# Board.net
KiCad netlist of a schematic drawn in EAGLE
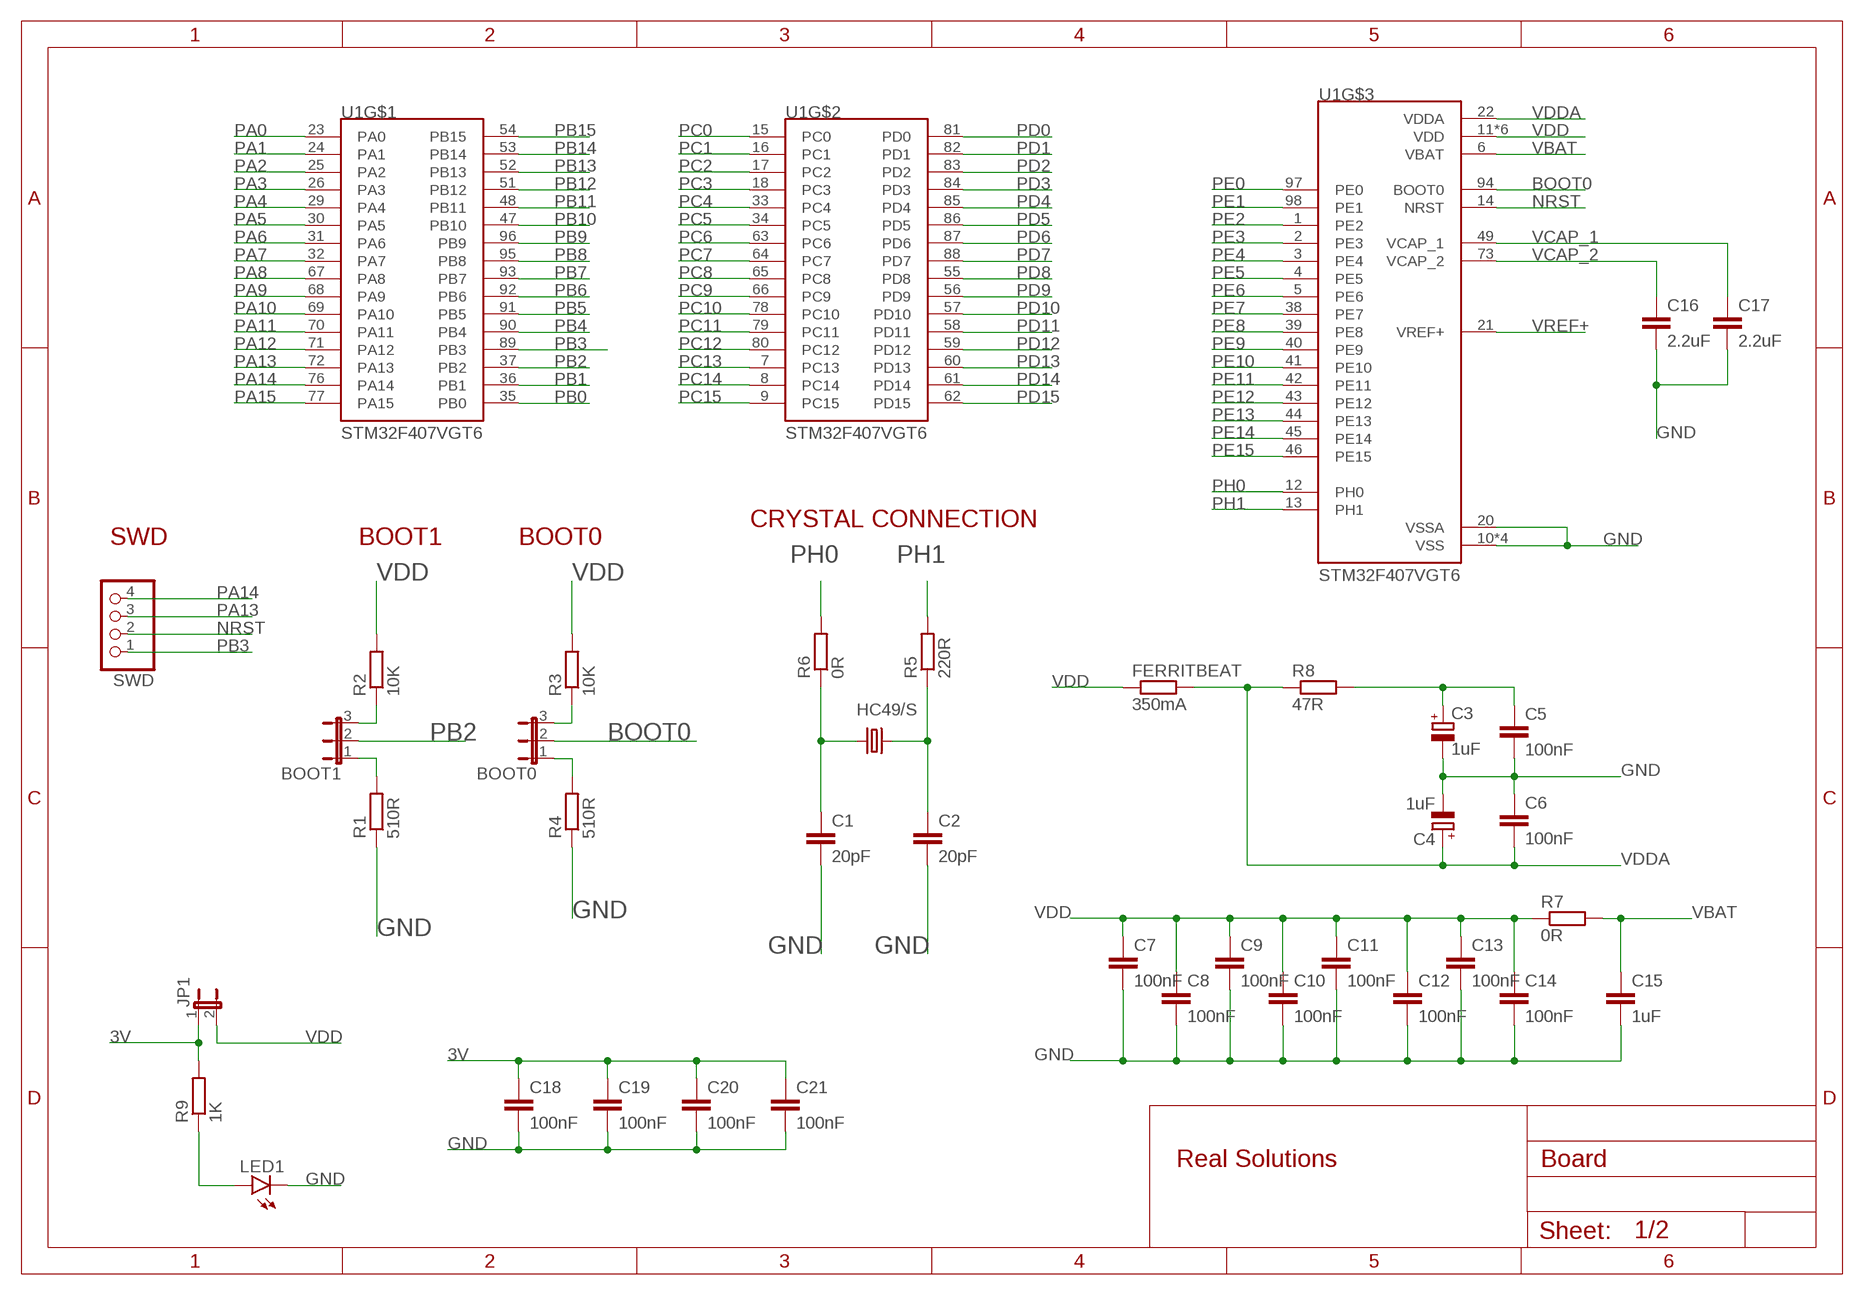
[diagram p0: schematic, sheet 1]
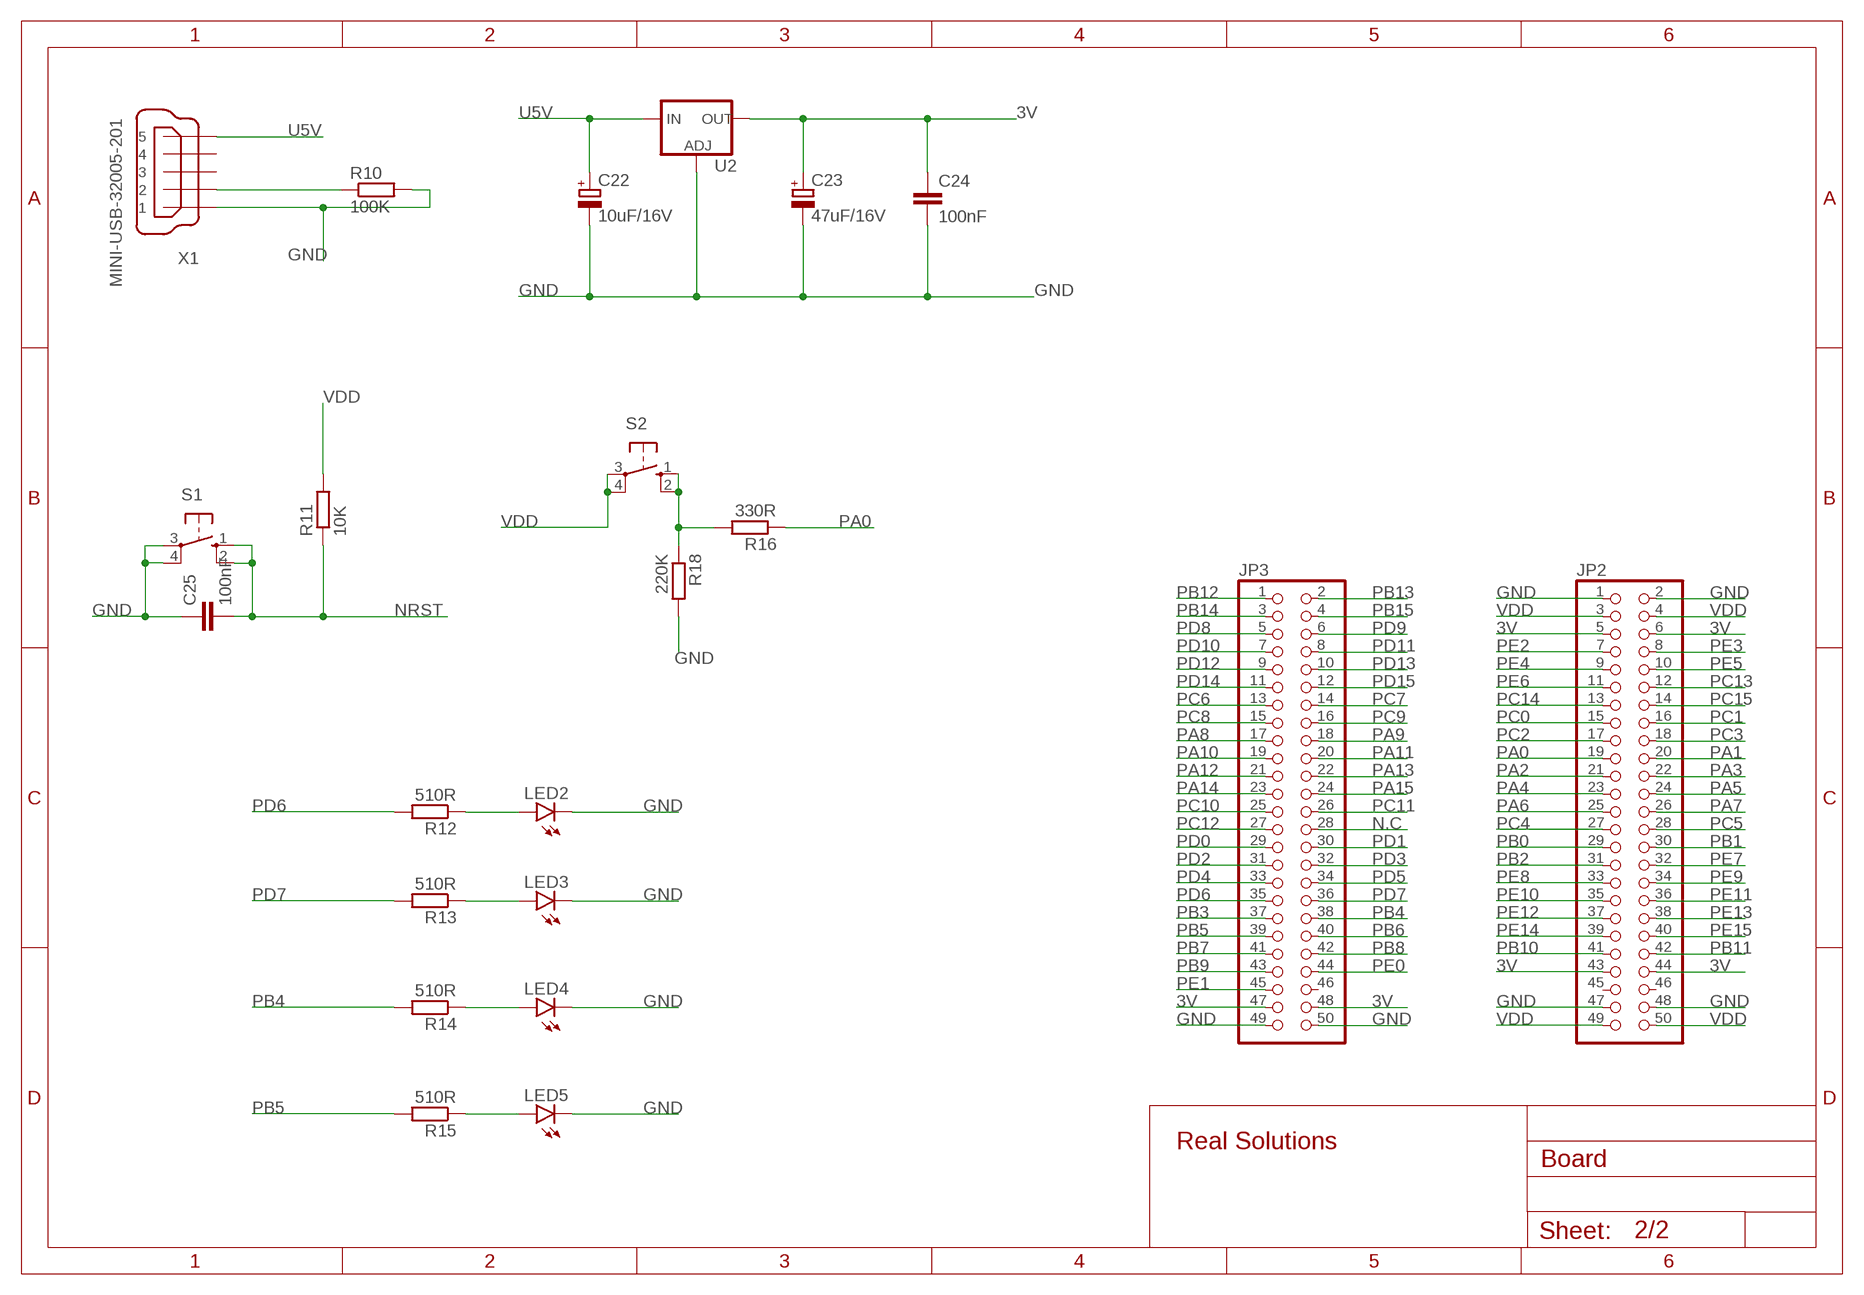
[diagram p1: schematic, sheet 2]

(export (version "E")
  (design (tool "Eeschema 10.0.6"))
  (components
    (comp (ref "BOOT0")
      (value "JP2E")
      (footprint "eagle-import:JP2")
      (libsource (lib "eagle-import") (part "JP2E"))
    )
    (comp (ref "BOOT1")
      (value "JP2E")
      (footprint "eagle-import:JP2")
      (libsource (lib "eagle-import") (part "JP2E"))
    )
    (comp (ref "C1")
      (value "20pF")
      (footprint "eagle-import:C0805")
      (libsource (lib "eagle-import") (part "C-EUC0805"))
    )
    (comp (ref "C2")
      (value "20pF")
      (footprint "eagle-import:C0805")
      (libsource (lib "eagle-import") (part "C-EUC0805"))
    )
    (comp (ref "C3")
      (value "1uF")
      (footprint "eagle-import:SMC_A")
      (libsource (lib "eagle-import") (part "CPOL-EUSMCA"))
    )
    (comp (ref "C4")
      (value "1uF")
      (footprint "eagle-import:SMC_A")
      (libsource (lib "eagle-import") (part "CPOL-EUSMCA"))
    )
    (comp (ref "C5")
      (value "100nF")
      (footprint "eagle-import:C0805")
      (libsource (lib "eagle-import") (part "C-EUC0805"))
    )
    (comp (ref "C6")
      (value "100nF")
      (footprint "eagle-import:C0805")
      (libsource (lib "eagle-import") (part "C-EUC0805"))
    )
    (comp (ref "C7")
      (value "100nF")
      (footprint "eagle-import:C0805")
      (libsource (lib "eagle-import") (part "C-EUC0805"))
    )
    (comp (ref "C8")
      (value "100nF")
      (footprint "eagle-import:C0805")
      (libsource (lib "eagle-import") (part "C-EUC0805"))
    )
    (comp (ref "C9")
      (value "100nF")
      (footprint "eagle-import:C0805")
      (libsource (lib "eagle-import") (part "C-EUC0805"))
    )
    (comp (ref "C10")
      (value "100nF")
      (footprint "eagle-import:C0805")
      (libsource (lib "eagle-import") (part "C-EUC0805"))
    )
    (comp (ref "C11")
      (value "100nF")
      (footprint "eagle-import:C0805")
      (libsource (lib "eagle-import") (part "C-EUC0805"))
    )
    (comp (ref "C12")
      (value "100nF")
      (footprint "eagle-import:C0805")
      (libsource (lib "eagle-import") (part "C-EUC0805"))
    )
    (comp (ref "C13")
      (value "100nF")
      (footprint "eagle-import:C0805")
      (libsource (lib "eagle-import") (part "C-EUC0805"))
    )
    (comp (ref "C14")
      (value "100nF")
      (footprint "eagle-import:C0805")
      (libsource (lib "eagle-import") (part "C-EUC0805"))
    )
    (comp (ref "C15")
      (value "1uF")
      (footprint "eagle-import:C0805")
      (libsource (lib "eagle-import") (part "C-EUC0805"))
    )
    (comp (ref "C16")
      (value "2.2uF")
      (footprint "eagle-import:C0805")
      (libsource (lib "eagle-import") (part "C-EUC0805"))
    )
    (comp (ref "C17")
      (value "2.2uF")
      (footprint "eagle-import:C0805")
      (libsource (lib "eagle-import") (part "C-EUC0805"))
    )
    (comp (ref "C18")
      (value "100nF")
      (footprint "eagle-import:C0805")
      (libsource (lib "eagle-import") (part "C-EUC0805"))
    )
    (comp (ref "C19")
      (value "100nF")
      (footprint "eagle-import:C0805")
      (libsource (lib "eagle-import") (part "C-EUC0805"))
    )
    (comp (ref "C20")
      (value "100nF")
      (footprint "eagle-import:C0805")
      (libsource (lib "eagle-import") (part "C-EUC0805"))
    )
    (comp (ref "C21")
      (value "100nF")
      (footprint "eagle-import:C0805")
      (libsource (lib "eagle-import") (part "C-EUC0805"))
    )
    (comp (ref "FERRITBEAT")
      (value "350mA")
      (footprint "eagle-import:R1206")
      (libsource (lib "eagle-import") (part "R-EU_R1206"))
    )
    (comp (ref "HC49/S")
      (value "CRYSTALHC49S")
      (footprint "eagle-import:HC49_S")
      (libsource (lib "eagle-import") (part "CRYSTALHC49S"))
    )
    (comp (ref "JP1")
      (value "JP1E")
      (footprint "eagle-import:JP1")
      (libsource (lib "eagle-import") (part "JP1E"))
    )
    (comp (ref "LED1")
      (value "LEDCHIP-LED0805")
      (footprint "eagle-import:CHIP-LED0805")
      (libsource (lib "eagle-import") (part "LEDCHIP-LED0805"))
    )
    (comp (ref "R1")
      (value "510R")
      (footprint "eagle-import:R0805")
      (libsource (lib "eagle-import") (part "R-EU_R0805"))
    )
    (comp (ref "R2")
      (value "10K")
      (footprint "eagle-import:R0805")
      (libsource (lib "eagle-import") (part "R-EU_R0805"))
    )
    (comp (ref "R3")
      (value "10K")
      (footprint "eagle-import:R0805")
      (libsource (lib "eagle-import") (part "R-EU_R0805"))
    )
    (comp (ref "R4")
      (value "510R")
      (footprint "eagle-import:R0805")
      (libsource (lib "eagle-import") (part "R-EU_R0805"))
    )
    (comp (ref "R5")
      (value "220R")
      (footprint "eagle-import:R0805")
      (libsource (lib "eagle-import") (part "R-EU_R0805"))
    )
    (comp (ref "R6")
      (value "0R")
      (footprint "eagle-import:R0805")
      (libsource (lib "eagle-import") (part "R-EU_R0805"))
    )
    (comp (ref "R7")
      (value "0R")
      (footprint "eagle-import:R0805")
      (libsource (lib "eagle-import") (part "R-EU_R0805"))
    )
    (comp (ref "R8")
      (value "47R")
      (footprint "eagle-import:R0805")
      (libsource (lib "eagle-import") (part "R-EU_R0805"))
    )
    (comp (ref "R9")
      (value "1K")
      (footprint "eagle-import:R0805")
      (libsource (lib "eagle-import") (part "R-EU_R0805"))
    )
    (comp (ref "SWD")
      (value "PINHD-1X4")
      (footprint "eagle-import:1X04")
      (libsource (lib "eagle-import") (part "PINHD-1X4"))
    )
    (comp (ref "U1")
      (value "STM32F407VGT6")
      (footprint "eagle-import:QFP50P1600X1600X160-100N")
      (fields (field (name "MF") "STMicroelectronics"))
      (libsource (lib "eagle-import") (part "STM32F407VGT6"))
    )
    (comp (ref "C22")
      (value "10uF/16V")
      (footprint "eagle-import:153CLV-0405")
      (libsource (lib "eagle-import") (part "CPOL-EU153CLV-0405"))
    )
    (comp (ref "C23")
      (value "47uF/16V")
      (footprint "eagle-import:153CLV-0605")
      (libsource (lib "eagle-import") (part "CPOL-EU153CLV-0605"))
    )
    (comp (ref "C24")
      (value "100nF")
      (footprint "eagle-import:C0805")
      (libsource (lib "eagle-import") (part "C-EUC0805"))
    )
    (comp (ref "C25")
      (value "100nF")
      (footprint "eagle-import:C0805")
      (libsource (lib "eagle-import") (part "C-EUC0805"))
    )
    (comp (ref "JP2")
      (value "PINHD-2X25")
      (footprint "eagle-import:2X25")
      (libsource (lib "eagle-import") (part "PINHD-2X25"))
    )
    (comp (ref "JP3")
      (value "PINHD-2X25")
      (footprint "eagle-import:2X25")
      (libsource (lib "eagle-import") (part "PINHD-2X25"))
    )
    (comp (ref "LED2")
      (value "LEDCHIP-LED0805")
      (footprint "eagle-import:CHIP-LED0805")
      (libsource (lib "eagle-import") (part "LEDCHIP-LED0805"))
    )
    (comp (ref "LED3")
      (value "LEDCHIP-LED0805")
      (footprint "eagle-import:CHIP-LED0805")
      (libsource (lib "eagle-import") (part "LEDCHIP-LED0805"))
    )
    (comp (ref "LED4")
      (value "LEDCHIP-LED0805")
      (footprint "eagle-import:CHIP-LED0805")
      (libsource (lib "eagle-import") (part "LEDCHIP-LED0805"))
    )
    (comp (ref "LED5")
      (value "LEDCHIP-LED0805")
      (footprint "eagle-import:CHIP-LED0805")
      (libsource (lib "eagle-import") (part "LEDCHIP-LED0805"))
    )
    (comp (ref "R10")
      (value "100K")
      (footprint "eagle-import:R0805")
      (libsource (lib "eagle-import") (part "R-EU_R0805"))
    )
    (comp (ref "R11")
      (value "10K")
      (footprint "eagle-import:R0805")
      (libsource (lib "eagle-import") (part "R-EU_R0805"))
    )
    (comp (ref "R12")
      (value "510R")
      (footprint "eagle-import:R0805")
      (libsource (lib "eagle-import") (part "R-EU_R0805"))
    )
    (comp (ref "R13")
      (value "510R")
      (footprint "eagle-import:R0805")
      (libsource (lib "eagle-import") (part "R-EU_R0805"))
    )
    (comp (ref "R14")
      (value "510R")
      (footprint "eagle-import:R0805")
      (libsource (lib "eagle-import") (part "R-EU_R0805"))
    )
    (comp (ref "R15")
      (value "510R")
      (footprint "eagle-import:R0805")
      (libsource (lib "eagle-import") (part "R-EU_R0805"))
    )
    (comp (ref "R16")
      (value "330R")
      (footprint "eagle-import:R0805")
      (libsource (lib "eagle-import") (part "R-EU_R0805"))
    )
    (comp (ref "R18")
      (value "220K")
      (footprint "eagle-import:R0805")
      (libsource (lib "eagle-import") (part "R-EU_R0805"))
    )
    (comp (ref "S1")
      (value "10-XX")
      (footprint "eagle-import:B3F-10XX")
      (fields (field (name "MPN") "B3F-1000"))
      (libsource (lib "eagle-import") (part "10-XX"))
    )
    (comp (ref "S2")
      (value "10-XX")
      (footprint "eagle-import:B3F-10XX")
      (fields (field (name "MPN") "B3F-1000"))
      (libsource (lib "eagle-import") (part "10-XX"))
    )
    (comp (ref "U2")
      (value "V_REG_LM1117SOT223")
      (footprint "eagle-import:SOT223")
      (libsource (lib "eagle-import") (part "V_REG_LM1117SOT223"))
    )
    (comp (ref "X1")
      (value "MINI-USB-32005-201")
      (footprint "eagle-import:32005-201")
      (libsource (lib "eagle-import") (part "MINI-USB-32005-201"))
    )
  )
  (nets
    (net (code "1") (name "3V") (class "Default")
      (node (ref "C18") (pin "1") (pinfunction "1_1") (pintype "passive"))
      (node (ref "C19") (pin "1") (pinfunction "1_1") (pintype "passive"))
      (node (ref "C20") (pin "1") (pinfunction "1_1") (pintype "passive"))
      (node (ref "C21") (pin "1") (pinfunction "1_1") (pintype "passive"))
      (node (ref "C23") (pin "+") (pinfunction "+_+") (pintype "passive"))
      (node (ref "C24") (pin "1") (pinfunction "1_1") (pintype "passive"))
      (node (ref "JP1") (pin "1") (pinfunction "1_1") (pintype "passive"))
      (node (ref "JP2") (pin "43") (pinfunction "43_43") (pintype "passive"))
      (node (ref "JP2") (pin "44") (pinfunction "44_44") (pintype "passive"))
      (node (ref "JP2") (pin "5") (pinfunction "5_5") (pintype "passive"))
      (node (ref "JP2") (pin "6") (pinfunction "6_6") (pintype "passive"))
      (node (ref "JP3") (pin "47") (pinfunction "47_47") (pintype "passive"))
      (node (ref "JP3") (pin "48") (pinfunction "48_48") (pintype "passive"))
      (node (ref "R9") (pin "2") (pinfunction "2_2") (pintype "passive"))
      (node (ref "U2") (pin "2") (pinfunction "OUT_2") (pintype "output"))
      (node (ref "U2") (pin "4") (pinfunction "OUT_4") (pintype "output"))
    )
    (net (code "2") (name "BOOT0") (class "Default")
      (node (ref "BOOT0") (pin "2") (pinfunction "2_2") (pintype "passive"))
      (node (ref "U1") (pin "94") (pinfunction "BOOT0_94") (pintype "input"))
    )
    (net (code "3") (name "GND") (class "Default")
      (node (ref "C1") (pin "2") (pinfunction "2_2") (pintype "passive"))
      (node (ref "C10") (pin "2") (pinfunction "2_2") (pintype "passive"))
      (node (ref "C11") (pin "2") (pinfunction "2_2") (pintype "passive"))
      (node (ref "C12") (pin "2") (pinfunction "2_2") (pintype "passive"))
      (node (ref "C13") (pin "2") (pinfunction "2_2") (pintype "passive"))
      (node (ref "C14") (pin "2") (pinfunction "2_2") (pintype "passive"))
      (node (ref "C15") (pin "2") (pinfunction "2_2") (pintype "passive"))
      (node (ref "C16") (pin "2") (pinfunction "2_2") (pintype "passive"))
      (node (ref "C17") (pin "2") (pinfunction "2_2") (pintype "passive"))
      (node (ref "C18") (pin "2") (pinfunction "2_2") (pintype "passive"))
      (node (ref "C19") (pin "2") (pinfunction "2_2") (pintype "passive"))
      (node (ref "C2") (pin "2") (pinfunction "2_2") (pintype "passive"))
      (node (ref "C20") (pin "2") (pinfunction "2_2") (pintype "passive"))
      (node (ref "C21") (pin "2") (pinfunction "2_2") (pintype "passive"))
      (node (ref "C22") (pin "-") (pinfunction "-_-") (pintype "passive"))
      (node (ref "C23") (pin "-") (pinfunction "-_-") (pintype "passive"))
      (node (ref "C24") (pin "2") (pinfunction "2_2") (pintype "passive"))
      (node (ref "C25") (pin "1") (pinfunction "1_1") (pintype "passive"))
      (node (ref "C3") (pin "-") (pinfunction "-_-") (pintype "passive"))
      (node (ref "C4") (pin "-") (pinfunction "-_-") (pintype "passive"))
      (node (ref "C5") (pin "2") (pinfunction "2_2") (pintype "passive"))
      (node (ref "C6") (pin "1") (pinfunction "1_1") (pintype "passive"))
      (node (ref "C7") (pin "2") (pinfunction "2_2") (pintype "passive"))
      (node (ref "C8") (pin "2") (pinfunction "2_2") (pintype "passive"))
      (node (ref "C9") (pin "2") (pinfunction "2_2") (pintype "passive"))
      (node (ref "JP2") (pin "1") (pinfunction "1_1") (pintype "passive"))
      (node (ref "JP2") (pin "2") (pinfunction "2_2") (pintype "passive"))
      (node (ref "JP2") (pin "47") (pinfunction "47_47") (pintype "passive"))
      (node (ref "JP2") (pin "48") (pinfunction "48_48") (pintype "passive"))
      (node (ref "JP3") (pin "49") (pinfunction "49_49") (pintype "passive"))
      (node (ref "JP3") (pin "50") (pinfunction "50_50") (pintype "passive"))
      (node (ref "LED1") (pin "C") (pinfunction "C_C") (pintype "passive"))
      (node (ref "LED2") (pin "C") (pinfunction "C_C") (pintype "passive"))
      (node (ref "LED3") (pin "C") (pinfunction "C_C") (pintype "passive"))
      (node (ref "LED4") (pin "C") (pinfunction "C_C") (pintype "passive"))
      (node (ref "LED5") (pin "C") (pinfunction "C_C") (pintype "passive"))
      (node (ref "R1") (pin "1") (pinfunction "1_1") (pintype "passive"))
      (node (ref "R10") (pin "2") (pinfunction "2_2") (pintype "passive"))
      (node (ref "R18") (pin "2") (pinfunction "2_2") (pintype "passive"))
      (node (ref "R4") (pin "1") (pinfunction "1_1") (pintype "passive"))
      (node (ref "S1") (pin "3") (pinfunction "P_3") (pintype "passive"))
      (node (ref "S1") (pin "4") (pinfunction "P1_4") (pintype "passive"))
      (node (ref "U1") (pin "10") (pinfunction "VSS_10") (pintype "power_in"))
      (node (ref "U1") (pin "20") (pinfunction "VSSA_20") (pintype "power_in"))
      (node (ref "U1") (pin "27") (pinfunction "VSS_27") (pintype "power_in"))
      (node (ref "U1") (pin "74") (pinfunction "VSS_74") (pintype "power_in"))
      (node (ref "U1") (pin "99") (pinfunction "VSS_99") (pintype "power_in"))
      (node (ref "U2") (pin "1") (pinfunction "ADJ_1") (pintype "input"))
      (node (ref "X1") (pin "1") (pinfunction "1_1") (pintype "passive"))
    )
    (net (code "4") (name "N.C") (class "Default")
      (node (ref "JP3") (pin "28") (pinfunction "28_28") (pintype "passive"))
    )
    (net (code "5") (name "NRST") (class "Default")
      (node (ref "C25") (pin "2") (pinfunction "2_2") (pintype "passive"))
      (node (ref "R11") (pin "1") (pinfunction "1_1") (pintype "passive"))
      (node (ref "S1") (pin "1") (pinfunction "S_1") (pintype "passive"))
      (node (ref "S1") (pin "2") (pinfunction "S1_2") (pintype "passive"))
      (node (ref "SWD") (pin "2") (pinfunction "2_2") (pintype "passive"))
      (node (ref "U1") (pin "14") (pinfunction "NRST_14") (pintype "bidirectional"))
    )
    (net (code "6") (name "Net-(BOOT0-Pad1)") (class "Default")
      (node (ref "BOOT0") (pin "1") (pinfunction "1_1") (pintype "passive"))
      (node (ref "R4") (pin "2") (pinfunction "2_2") (pintype "passive"))
    )
    (net (code "7") (name "Net-(BOOT0-Pad3)") (class "Default")
      (node (ref "BOOT0") (pin "3") (pinfunction "3_3") (pintype "passive"))
      (node (ref "R3") (pin "1") (pinfunction "1_1") (pintype "passive"))
    )
    (net (code "8") (name "Net-(BOOT1-Pad1)") (class "Default")
      (node (ref "BOOT1") (pin "1") (pinfunction "1_1") (pintype "passive"))
      (node (ref "R1") (pin "2") (pinfunction "2_2") (pintype "passive"))
    )
    (net (code "9") (name "Net-(BOOT1-Pad3)") (class "Default")
      (node (ref "BOOT1") (pin "3") (pinfunction "3_3") (pintype "passive"))
      (node (ref "R2") (pin "1") (pinfunction "1_1") (pintype "passive"))
    )
    (net (code "10") (name "Net-(C1-Pad1)") (class "Default")
      (node (ref "C1") (pin "1") (pinfunction "1_1") (pintype "passive"))
      (node (ref "HC49/S") (pin "1") (pinfunction "1_1") (pintype "passive"))
      (node (ref "R6") (pin "1") (pinfunction "1_1") (pintype "passive"))
    )
    (net (code "11") (name "Net-(C2-Pad1)") (class "Default")
      (node (ref "C2") (pin "1") (pinfunction "1_1") (pintype "passive"))
      (node (ref "HC49/S") (pin "2") (pinfunction "2_2") (pintype "passive"))
      (node (ref "R5") (pin "1") (pinfunction "1_1") (pintype "passive"))
    )
    (net (code "12") (name "Net-(C3-Pad+)") (class "Default")
      (node (ref "C3") (pin "+") (pinfunction "+_+") (pintype "passive"))
      (node (ref "C5") (pin "1") (pinfunction "1_1") (pintype "passive"))
      (node (ref "R8") (pin "2") (pinfunction "2_2") (pintype "passive"))
    )
    (net (code "13") (name "Net-(LED1-PadA)") (class "Default")
      (node (ref "LED1") (pin "A") (pinfunction "A_A") (pintype "passive"))
      (node (ref "R9") (pin "1") (pinfunction "1_1") (pintype "passive"))
    )
    (net (code "14") (name "Net-(LED2-PadA)") (class "Default")
      (node (ref "LED2") (pin "A") (pinfunction "A_A") (pintype "passive"))
      (node (ref "R12") (pin "1") (pinfunction "1_1") (pintype "passive"))
    )
    (net (code "15") (name "Net-(LED3-PadA)") (class "Default")
      (node (ref "LED3") (pin "A") (pinfunction "A_A") (pintype "passive"))
      (node (ref "R13") (pin "1") (pinfunction "1_1") (pintype "passive"))
    )
    (net (code "16") (name "Net-(LED4-PadA)") (class "Default")
      (node (ref "LED4") (pin "A") (pinfunction "A_A") (pintype "passive"))
      (node (ref "R14") (pin "1") (pinfunction "1_1") (pintype "passive"))
    )
    (net (code "17") (name "Net-(LED5-PadA)") (class "Default")
      (node (ref "LED5") (pin "A") (pinfunction "A_A") (pintype "passive"))
      (node (ref "R15") (pin "1") (pinfunction "1_1") (pintype "passive"))
    )
    (net (code "18") (name "Net-(R10-Pad1)") (class "Default")
      (node (ref "R10") (pin "1") (pinfunction "1_1") (pintype "passive"))
      (node (ref "X1") (pin "2") (pinfunction "2_2") (pintype "passive"))
    )
    (net (code "19") (name "Net-(S2-S)") (class "Default")
      (node (ref "R16") (pin "2") (pinfunction "2_2") (pintype "passive"))
      (node (ref "R18") (pin "1") (pinfunction "1_1") (pintype "passive"))
      (node (ref "S2") (pin "1") (pinfunction "S_1") (pintype "passive"))
      (node (ref "S2") (pin "2") (pinfunction "S1_2") (pintype "passive"))
    )
    (net (code "20") (name "PA0") (class "Default")
      (node (ref "JP2") (pin "19") (pinfunction "19_19") (pintype "passive"))
      (node (ref "R16") (pin "1") (pinfunction "1_1") (pintype "passive"))
      (node (ref "U1") (pin "23") (pinfunction "PA0_23") (pintype "bidirectional"))
    )
    (net (code "21") (name "PA1") (class "Default")
      (node (ref "JP2") (pin "20") (pinfunction "20_20") (pintype "passive"))
      (node (ref "U1") (pin "24") (pinfunction "PA1_24") (pintype "bidirectional"))
    )
    (net (code "22") (name "PA2") (class "Default")
      (node (ref "JP2") (pin "21") (pinfunction "21_21") (pintype "passive"))
      (node (ref "U1") (pin "25") (pinfunction "PA2_25") (pintype "bidirectional"))
    )
    (net (code "23") (name "PA3") (class "Default")
      (node (ref "JP2") (pin "22") (pinfunction "22_22") (pintype "passive"))
      (node (ref "U1") (pin "26") (pinfunction "PA3_26") (pintype "bidirectional"))
    )
    (net (code "24") (name "PA4") (class "Default")
      (node (ref "JP2") (pin "23") (pinfunction "23_23") (pintype "passive"))
      (node (ref "U1") (pin "29") (pinfunction "PA4_29") (pintype "bidirectional"))
    )
    (net (code "25") (name "PA5") (class "Default")
      (node (ref "JP2") (pin "24") (pinfunction "24_24") (pintype "passive"))
      (node (ref "U1") (pin "30") (pinfunction "PA5_30") (pintype "bidirectional"))
    )
    (net (code "26") (name "PA6") (class "Default")
      (node (ref "JP2") (pin "25") (pinfunction "25_25") (pintype "passive"))
      (node (ref "U1") (pin "31") (pinfunction "PA6_31") (pintype "bidirectional"))
    )
    (net (code "27") (name "PA7") (class "Default")
      (node (ref "JP2") (pin "26") (pinfunction "26_26") (pintype "passive"))
      (node (ref "U1") (pin "32") (pinfunction "PA7_32") (pintype "bidirectional"))
    )
    (net (code "28") (name "PA8") (class "Default")
      (node (ref "JP3") (pin "17") (pinfunction "17_17") (pintype "passive"))
      (node (ref "U1") (pin "67") (pinfunction "PA8_67") (pintype "bidirectional"))
    )
    (net (code "29") (name "PA9") (class "Default")
      (node (ref "JP3") (pin "18") (pinfunction "18_18") (pintype "passive"))
      (node (ref "U1") (pin "68") (pinfunction "PA9_68") (pintype "bidirectional"))
    )
    (net (code "30") (name "PA10") (class "Default")
      (node (ref "JP3") (pin "19") (pinfunction "19_19") (pintype "passive"))
      (node (ref "U1") (pin "69") (pinfunction "PA10_69") (pintype "bidirectional"))
    )
    (net (code "31") (name "PA11") (class "Default")
      (node (ref "JP3") (pin "20") (pinfunction "20_20") (pintype "passive"))
      (node (ref "U1") (pin "70") (pinfunction "PA11_70") (pintype "bidirectional"))
    )
    (net (code "32") (name "PA12") (class "Default")
      (node (ref "JP3") (pin "21") (pinfunction "21_21") (pintype "passive"))
      (node (ref "U1") (pin "71") (pinfunction "PA12_71") (pintype "bidirectional"))
    )
    (net (code "33") (name "PA13") (class "Default")
      (node (ref "JP3") (pin "22") (pinfunction "22_22") (pintype "passive"))
      (node (ref "SWD") (pin "3") (pinfunction "3_3") (pintype "passive"))
      (node (ref "U1") (pin "72") (pinfunction "PA13_72") (pintype "bidirectional"))
    )
    (net (code "34") (name "PA14") (class "Default")
      (node (ref "JP3") (pin "23") (pinfunction "23_23") (pintype "passive"))
      (node (ref "SWD") (pin "4") (pinfunction "4_4") (pintype "passive"))
      (node (ref "U1") (pin "76") (pinfunction "PA14_76") (pintype "bidirectional"))
    )
    (net (code "35") (name "PA15") (class "Default")
      (node (ref "JP3") (pin "24") (pinfunction "24_24") (pintype "passive"))
      (node (ref "U1") (pin "77") (pinfunction "PA15_77") (pintype "bidirectional"))
    )
    (net (code "36") (name "PB0") (class "Default")
      (node (ref "JP2") (pin "29") (pinfunction "29_29") (pintype "passive"))
      (node (ref "U1") (pin "35") (pinfunction "PB0_35") (pintype "bidirectional"))
    )
    (net (code "37") (name "PB1") (class "Default")
      (node (ref "JP2") (pin "30") (pinfunction "30_30") (pintype "passive"))
      (node (ref "U1") (pin "36") (pinfunction "PB1_36") (pintype "bidirectional"))
    )
    (net (code "38") (name "PB2") (class "Default")
      (node (ref "BOOT1") (pin "2") (pinfunction "2_2") (pintype "passive"))
      (node (ref "JP2") (pin "31") (pinfunction "31_31") (pintype "passive"))
      (node (ref "U1") (pin "37") (pinfunction "PB2_37") (pintype "bidirectional"))
    )
    (net (code "39") (name "PB3") (class "Default")
      (node (ref "JP3") (pin "37") (pinfunction "37_37") (pintype "passive"))
      (node (ref "SWD") (pin "1") (pinfunction "1_1") (pintype "passive"))
      (node (ref "U1") (pin "89") (pinfunction "PB3_89") (pintype "bidirectional"))
    )
    (net (code "40") (name "PB4") (class "Default")
      (node (ref "JP3") (pin "38") (pinfunction "38_38") (pintype "passive"))
      (node (ref "R14") (pin "2") (pinfunction "2_2") (pintype "passive"))
      (node (ref "U1") (pin "90") (pinfunction "PB4_90") (pintype "bidirectional"))
    )
    (net (code "41") (name "PB5") (class "Default")
      (node (ref "JP3") (pin "39") (pinfunction "39_39") (pintype "passive"))
      (node (ref "R15") (pin "2") (pinfunction "2_2") (pintype "passive"))
      (node (ref "U1") (pin "91") (pinfunction "PB5_91") (pintype "bidirectional"))
    )
    (net (code "42") (name "PB6") (class "Default")
      (node (ref "JP3") (pin "40") (pinfunction "40_40") (pintype "passive"))
      (node (ref "U1") (pin "92") (pinfunction "PB6_92") (pintype "bidirectional"))
    )
    (net (code "43") (name "PB7") (class "Default")
      (node (ref "JP3") (pin "41") (pinfunction "41_41") (pintype "passive"))
      (node (ref "U1") (pin "93") (pinfunction "PB7_93") (pintype "bidirectional"))
    )
    (net (code "44") (name "PB8") (class "Default")
      (node (ref "JP3") (pin "42") (pinfunction "42_42") (pintype "passive"))
      (node (ref "U1") (pin "95") (pinfunction "PB8_95") (pintype "bidirectional"))
    )
    (net (code "45") (name "PB9") (class "Default")
      (node (ref "JP3") (pin "43") (pinfunction "43_43") (pintype "passive"))
      (node (ref "U1") (pin "96") (pinfunction "PB9_96") (pintype "bidirectional"))
    )
    (net (code "46") (name "PB10") (class "Default")
      (node (ref "JP2") (pin "41") (pinfunction "41_41") (pintype "passive"))
      (node (ref "U1") (pin "47") (pinfunction "PB10_47") (pintype "bidirectional"))
    )
    (net (code "47") (name "PB11") (class "Default")
      (node (ref "JP2") (pin "42") (pinfunction "42_42") (pintype "passive"))
      (node (ref "U1") (pin "48") (pinfunction "PB11_48") (pintype "bidirectional"))
    )
    (net (code "48") (name "PB12") (class "Default")
      (node (ref "JP3") (pin "1") (pinfunction "1_1") (pintype "passive"))
      (node (ref "U1") (pin "51") (pinfunction "PB12_51") (pintype "bidirectional"))
    )
    (net (code "49") (name "PB13") (class "Default")
      (node (ref "JP3") (pin "2") (pinfunction "2_2") (pintype "passive"))
      (node (ref "U1") (pin "52") (pinfunction "PB13_52") (pintype "bidirectional"))
    )
    (net (code "50") (name "PB14") (class "Default")
      (node (ref "JP3") (pin "3") (pinfunction "3_3") (pintype "passive"))
      (node (ref "U1") (pin "53") (pinfunction "PB14_53") (pintype "bidirectional"))
    )
    (net (code "51") (name "PB15") (class "Default")
      (node (ref "JP3") (pin "4") (pinfunction "4_4") (pintype "passive"))
      (node (ref "U1") (pin "54") (pinfunction "PB15_54") (pintype "bidirectional"))
    )
    (net (code "52") (name "PC0") (class "Default")
      (node (ref "JP2") (pin "15") (pinfunction "15_15") (pintype "passive"))
      (node (ref "U1") (pin "15") (pinfunction "PC0_15") (pintype "bidirectional"))
    )
    (net (code "53") (name "PC1") (class "Default")
      (node (ref "JP2") (pin "16") (pinfunction "16_16") (pintype "passive"))
      (node (ref "U1") (pin "16") (pinfunction "PC1_16") (pintype "bidirectional"))
    )
    (net (code "54") (name "PC2") (class "Default")
      (node (ref "JP2") (pin "17") (pinfunction "17_17") (pintype "passive"))
      (node (ref "U1") (pin "17") (pinfunction "PC2_17") (pintype "bidirectional"))
    )
    (net (code "55") (name "PC3") (class "Default")
      (node (ref "JP2") (pin "18") (pinfunction "18_18") (pintype "passive"))
      (node (ref "U1") (pin "18") (pinfunction "PC3_18") (pintype "bidirectional"))
    )
    (net (code "56") (name "PC4") (class "Default")
      (node (ref "JP2") (pin "27") (pinfunction "27_27") (pintype "passive"))
      (node (ref "U1") (pin "33") (pinfunction "PC4_33") (pintype "bidirectional"))
    )
    (net (code "57") (name "PC5") (class "Default")
      (node (ref "JP2") (pin "28") (pinfunction "28_28") (pintype "passive"))
      (node (ref "U1") (pin "34") (pinfunction "PC5_34") (pintype "bidirectional"))
    )
    (net (code "58") (name "PC6") (class "Default")
      (node (ref "JP3") (pin "13") (pinfunction "13_13") (pintype "passive"))
      (node (ref "U1") (pin "63") (pinfunction "PC6_63") (pintype "bidirectional"))
    )
    (net (code "59") (name "PC7") (class "Default")
      (node (ref "JP3") (pin "14") (pinfunction "14_14") (pintype "passive"))
      (node (ref "U1") (pin "64") (pinfunction "PC7_64") (pintype "bidirectional"))
    )
    (net (code "60") (name "PC8") (class "Default")
      (node (ref "JP3") (pin "15") (pinfunction "15_15") (pintype "passive"))
      (node (ref "U1") (pin "65") (pinfunction "PC8_65") (pintype "bidirectional"))
    )
    (net (code "61") (name "PC9") (class "Default")
      (node (ref "JP3") (pin "16") (pinfunction "16_16") (pintype "passive"))
      (node (ref "U1") (pin "66") (pinfunction "PC9_66") (pintype "bidirectional"))
    )
    (net (code "62") (name "PC10") (class "Default")
      (node (ref "JP3") (pin "25") (pinfunction "25_25") (pintype "passive"))
      (node (ref "U1") (pin "78") (pinfunction "PC10_78") (pintype "bidirectional"))
    )
    (net (code "63") (name "PC11") (class "Default")
      (node (ref "JP3") (pin "26") (pinfunction "26_26") (pintype "passive"))
      (node (ref "U1") (pin "79") (pinfunction "PC11_79") (pintype "bidirectional"))
    )
    (net (code "64") (name "PC12") (class "Default")
      (node (ref "JP3") (pin "27") (pinfunction "27_27") (pintype "passive"))
      (node (ref "U1") (pin "80") (pinfunction "PC12_80") (pintype "bidirectional"))
    )
    (net (code "65") (name "PC13") (class "Default")
      (node (ref "JP2") (pin "12") (pinfunction "12_12") (pintype "passive"))
      (node (ref "U1") (pin "7") (pinfunction "PC13_7") (pintype "bidirectional"))
    )
    (net (code "66") (name "PC14") (class "Default")
      (node (ref "JP2") (pin "13") (pinfunction "13_13") (pintype "passive"))
      (node (ref "U1") (pin "8") (pinfunction "PC14_8") (pintype "bidirectional"))
    )
    (net (code "67") (name "PC15") (class "Default")
      (node (ref "JP2") (pin "14") (pinfunction "14_14") (pintype "passive"))
      (node (ref "U1") (pin "9") (pinfunction "PC15_9") (pintype "bidirectional"))
    )
    (net (code "68") (name "PD0") (class "Default")
      (node (ref "JP3") (pin "29") (pinfunction "29_29") (pintype "passive"))
      (node (ref "U1") (pin "81") (pinfunction "PD0_81") (pintype "bidirectional"))
    )
    (net (code "69") (name "PD1") (class "Default")
      (node (ref "JP3") (pin "30") (pinfunction "30_30") (pintype "passive"))
      (node (ref "U1") (pin "82") (pinfunction "PD1_82") (pintype "bidirectional"))
    )
    (net (code "70") (name "PD2") (class "Default")
      (node (ref "JP3") (pin "31") (pinfunction "31_31") (pintype "passive"))
      (node (ref "U1") (pin "83") (pinfunction "PD2_83") (pintype "bidirectional"))
    )
    (net (code "71") (name "PD3") (class "Default")
      (node (ref "JP3") (pin "32") (pinfunction "32_32") (pintype "passive"))
      (node (ref "U1") (pin "84") (pinfunction "PD3_84") (pintype "bidirectional"))
    )
    (net (code "72") (name "PD4") (class "Default")
      (node (ref "JP3") (pin "33") (pinfunction "33_33") (pintype "passive"))
      (node (ref "U1") (pin "85") (pinfunction "PD4_85") (pintype "bidirectional"))
    )
    (net (code "73") (name "PD5") (class "Default")
      (node (ref "JP3") (pin "34") (pinfunction "34_34") (pintype "passive"))
      (node (ref "U1") (pin "86") (pinfunction "PD5_86") (pintype "bidirectional"))
    )
    (net (code "74") (name "PD6") (class "Default")
      (node (ref "JP3") (pin "35") (pinfunction "35_35") (pintype "passive"))
      (node (ref "R12") (pin "2") (pinfunction "2_2") (pintype "passive"))
      (node (ref "U1") (pin "87") (pinfunction "PD6_87") (pintype "bidirectional"))
    )
    (net (code "75") (name "PD7") (class "Default")
      (node (ref "JP3") (pin "36") (pinfunction "36_36") (pintype "passive"))
      (node (ref "R13") (pin "2") (pinfunction "2_2") (pintype "passive"))
      (node (ref "U1") (pin "88") (pinfunction "PD7_88") (pintype "bidirectional"))
    )
    (net (code "76") (name "PD8") (class "Default")
      (node (ref "JP3") (pin "5") (pinfunction "5_5") (pintype "passive"))
      (node (ref "U1") (pin "55") (pinfunction "PD8_55") (pintype "bidirectional"))
    )
    (net (code "77") (name "PD9") (class "Default")
      (node (ref "JP3") (pin "6") (pinfunction "6_6") (pintype "passive"))
      (node (ref "U1") (pin "56") (pinfunction "PD9_56") (pintype "bidirectional"))
    )
    (net (code "78") (name "PD10") (class "Default")
      (node (ref "JP3") (pin "7") (pinfunction "7_7") (pintype "passive"))
      (node (ref "U1") (pin "57") (pinfunction "PD10_57") (pintype "bidirectional"))
    )
    (net (code "79") (name "PD11") (class "Default")
      (node (ref "JP3") (pin "8") (pinfunction "8_8") (pintype "passive"))
      (node (ref "U1") (pin "58") (pinfunction "PD11_58") (pintype "bidirectional"))
    )
    (net (code "80") (name "PD12") (class "Default")
      (node (ref "JP3") (pin "9") (pinfunction "9_9") (pintype "passive"))
      (node (ref "U1") (pin "59") (pinfunction "PD12_59") (pintype "bidirectional"))
    )
    (net (code "81") (name "PD13") (class "Default")
      (node (ref "JP3") (pin "10") (pinfunction "10_10") (pintype "passive"))
      (node (ref "U1") (pin "60") (pinfunction "PD13_60") (pintype "bidirectional"))
    )
    (net (code "82") (name "PD14") (class "Default")
      (node (ref "JP3") (pin "11") (pinfunction "11_11") (pintype "passive"))
      (node (ref "U1") (pin "61") (pinfunction "PD14_61") (pintype "bidirectional"))
    )
    (net (code "83") (name "PD15") (class "Default")
      (node (ref "JP3") (pin "12") (pinfunction "12_12") (pintype "passive"))
      (node (ref "U1") (pin "62") (pinfunction "PD15_62") (pintype "bidirectional"))
    )
    (net (code "84") (name "PE0") (class "Default")
      (node (ref "JP3") (pin "44") (pinfunction "44_44") (pintype "passive"))
      (node (ref "U1") (pin "97") (pinfunction "PE0_97") (pintype "bidirectional"))
    )
    (net (code "85") (name "PE1") (class "Default")
      (node (ref "JP3") (pin "45") (pinfunction "45_45") (pintype "passive"))
      (node (ref "U1") (pin "98") (pinfunction "PE1_98") (pintype "bidirectional"))
    )
    (net (code "86") (name "PE2") (class "Default")
      (node (ref "JP2") (pin "7") (pinfunction "7_7") (pintype "passive"))
      (node (ref "U1") (pin "1") (pinfunction "PE2_1") (pintype "bidirectional"))
    )
    (net (code "87") (name "PE3") (class "Default")
      (node (ref "JP2") (pin "8") (pinfunction "8_8") (pintype "passive"))
      (node (ref "U1") (pin "2") (pinfunction "PE3_2") (pintype "bidirectional"))
    )
    (net (code "88") (name "PE4") (class "Default")
      (node (ref "JP2") (pin "9") (pinfunction "9_9") (pintype "passive"))
      (node (ref "U1") (pin "3") (pinfunction "PE4_3") (pintype "bidirectional"))
    )
    (net (code "89") (name "PE5") (class "Default")
      (node (ref "JP2") (pin "10") (pinfunction "10_10") (pintype "passive"))
      (node (ref "U1") (pin "4") (pinfunction "PE5_4") (pintype "bidirectional"))
    )
    (net (code "90") (name "PE6") (class "Default")
      (node (ref "JP2") (pin "11") (pinfunction "11_11") (pintype "passive"))
      (node (ref "U1") (pin "5") (pinfunction "PE6_5") (pintype "bidirectional"))
    )
    (net (code "91") (name "PE7") (class "Default")
      (node (ref "JP2") (pin "32") (pinfunction "32_32") (pintype "passive"))
      (node (ref "U1") (pin "38") (pinfunction "PE7_38") (pintype "bidirectional"))
    )
    (net (code "92") (name "PE8") (class "Default")
      (node (ref "JP2") (pin "33") (pinfunction "33_33") (pintype "passive"))
      (node (ref "U1") (pin "39") (pinfunction "PE8_39") (pintype "bidirectional"))
    )
    (net (code "93") (name "PE9") (class "Default")
      (node (ref "JP2") (pin "34") (pinfunction "34_34") (pintype "passive"))
      (node (ref "U1") (pin "40") (pinfunction "PE9_40") (pintype "bidirectional"))
    )
    (net (code "94") (name "PE10") (class "Default")
      (node (ref "JP2") (pin "35") (pinfunction "35_35") (pintype "passive"))
      (node (ref "U1") (pin "41") (pinfunction "PE10_41") (pintype "bidirectional"))
    )
    (net (code "95") (name "PE11") (class "Default")
      (node (ref "JP2") (pin "36") (pinfunction "36_36") (pintype "passive"))
      (node (ref "U1") (pin "42") (pinfunction "PE11_42") (pintype "bidirectional"))
    )
    (net (code "96") (name "PE12") (class "Default")
      (node (ref "JP2") (pin "37") (pinfunction "37_37") (pintype "passive"))
      (node (ref "U1") (pin "43") (pinfunction "PE12_43") (pintype "bidirectional"))
    )
    (net (code "97") (name "PE13") (class "Default")
      (node (ref "JP2") (pin "38") (pinfunction "38_38") (pintype "passive"))
      (node (ref "U1") (pin "44") (pinfunction "PE13_44") (pintype "bidirectional"))
    )
    (net (code "98") (name "PE14") (class "Default")
      (node (ref "JP2") (pin "39") (pinfunction "39_39") (pintype "passive"))
      (node (ref "U1") (pin "45") (pinfunction "PE14_45") (pintype "bidirectional"))
    )
    (net (code "99") (name "PE15") (class "Default")
      (node (ref "JP2") (pin "40") (pinfunction "40_40") (pintype "passive"))
      (node (ref "U1") (pin "46") (pinfunction "PE15_46") (pintype "bidirectional"))
    )
    (net (code "100") (name "PH0") (class "Default")
      (node (ref "R6") (pin "2") (pinfunction "2_2") (pintype "passive"))
      (node (ref "U1") (pin "12") (pinfunction "PH0_12") (pintype "bidirectional"))
    )
    (net (code "101") (name "PH1") (class "Default")
      (node (ref "R5") (pin "2") (pinfunction "2_2") (pintype "passive"))
      (node (ref "U1") (pin "13") (pinfunction "PH1_13") (pintype "bidirectional"))
    )
    (net (code "102") (name "U5V") (class "Default")
      (node (ref "C22") (pin "+") (pinfunction "+_+") (pintype "passive"))
      (node (ref "U2") (pin "3") (pinfunction "IN_3") (pintype "input"))
      (node (ref "X1") (pin "5") (pinfunction "5_5") (pintype "passive"))
    )
    (net (code "103") (name "VBAT") (class "Default")
      (node (ref "C15") (pin "1") (pinfunction "1_1") (pintype "passive"))
      (node (ref "R7") (pin "2") (pinfunction "2_2") (pintype "passive"))
      (node (ref "U1") (pin "6") (pinfunction "VBAT_6") (pintype "power_in"))
    )
    (net (code "104") (name "VCAP_1") (class "Default")
      (node (ref "C17") (pin "1") (pinfunction "1_1") (pintype "passive"))
      (node (ref "U1") (pin "49") (pinfunction "VCAP_1_49") (pintype "passive"))
    )
    (net (code "105") (name "VCAP_2") (class "Default")
      (node (ref "C16") (pin "1") (pinfunction "1_1") (pintype "passive"))
      (node (ref "U1") (pin "73") (pinfunction "VCAP_2_73") (pintype "passive"))
    )
    (net (code "106") (name "VDD") (class "Default")
      (node (ref "C10") (pin "1") (pinfunction "1_1") (pintype "passive"))
      (node (ref "C11") (pin "1") (pinfunction "1_1") (pintype "passive"))
      (node (ref "C12") (pin "1") (pinfunction "1_1") (pintype "passive"))
      (node (ref "C13") (pin "1") (pinfunction "1_1") (pintype "passive"))
      (node (ref "C14") (pin "1") (pinfunction "1_1") (pintype "passive"))
      (node (ref "C7") (pin "1") (pinfunction "1_1") (pintype "passive"))
      (node (ref "C8") (pin "1") (pinfunction "1_1") (pintype "passive"))
      (node (ref "C9") (pin "1") (pinfunction "1_1") (pintype "passive"))
      (node (ref "FERRITBEAT") (pin "1") (pinfunction "1_1") (pintype "passive"))
      (node (ref "JP1") (pin "2") (pinfunction "2_2") (pintype "passive"))
      (node (ref "JP2") (pin "3") (pinfunction "3_3") (pintype "passive"))
      (node (ref "JP2") (pin "4") (pinfunction "4_4") (pintype "passive"))
      (node (ref "JP2") (pin "49") (pinfunction "49_49") (pintype "passive"))
      (node (ref "JP2") (pin "50") (pinfunction "50_50") (pintype "passive"))
      (node (ref "R11") (pin "2") (pinfunction "2_2") (pintype "passive"))
      (node (ref "R2") (pin "2") (pinfunction "2_2") (pintype "passive"))
      (node (ref "R3") (pin "2") (pinfunction "2_2") (pintype "passive"))
      (node (ref "R7") (pin "1") (pinfunction "1_1") (pintype "passive"))
      (node (ref "S2") (pin "3") (pinfunction "P_3") (pintype "passive"))
      (node (ref "S2") (pin "4") (pinfunction "P1_4") (pintype "passive"))
      (node (ref "U1") (pin "100") (pinfunction "VDD_100") (pintype "power_in"))
      (node (ref "U1") (pin "11") (pinfunction "VDD_11") (pintype "power_in"))
      (node (ref "U1") (pin "19") (pinfunction "VDD_19") (pintype "power_in"))
      (node (ref "U1") (pin "28") (pinfunction "VDD_28") (pintype "power_in"))
      (node (ref "U1") (pin "50") (pinfunction "VDD_50") (pintype "power_in"))
      (node (ref "U1") (pin "75") (pinfunction "VDD_75") (pintype "power_in"))
    )
    (net (code "107") (name "VDDA") (class "Default")
      (node (ref "C4") (pin "+") (pinfunction "+_+") (pintype "passive"))
      (node (ref "C6") (pin "2") (pinfunction "2_2") (pintype "passive"))
      (node (ref "FERRITBEAT") (pin "2") (pinfunction "2_2") (pintype "passive"))
      (node (ref "R8") (pin "1") (pinfunction "1_1") (pintype "passive"))
      (node (ref "U1") (pin "22") (pinfunction "VDDA_22") (pintype "power_in"))
    )
    (net (code "108") (name "VREF+") (class "Default")
      (node (ref "U1") (pin "21") (pinfunction "VREF+_21") (pintype "power_in"))
    )
    (net (code "109") (name "unconnected-(JP2-Pad45)") (class "Default")
      (node (ref "JP2") (pin "45") (pinfunction "45_45") (pintype "passive"))
    )
    (net (code "110") (name "unconnected-(JP2-Pad46)") (class "Default")
      (node (ref "JP2") (pin "46") (pinfunction "46_46") (pintype "passive"))
    )
    (net (code "111") (name "unconnected-(JP3-Pad46)") (class "Default")
      (node (ref "JP3") (pin "46") (pinfunction "46_46") (pintype "passive"))
    )
    (net (code "112") (name "unconnected-(X1-Pad3)") (class "Default")
      (node (ref "X1") (pin "3") (pinfunction "3_3") (pintype "passive"))
    )
    (net (code "113") (name "unconnected-(X1-Pad4)") (class "Default")
      (node (ref "X1") (pin "4") (pinfunction "4_4") (pintype "passive"))
    )
  )
)
